# EasyEDA_-_Encoder_Breakout_Schematic.net
KiCad netlist of a schematic drawn in EasyEDA
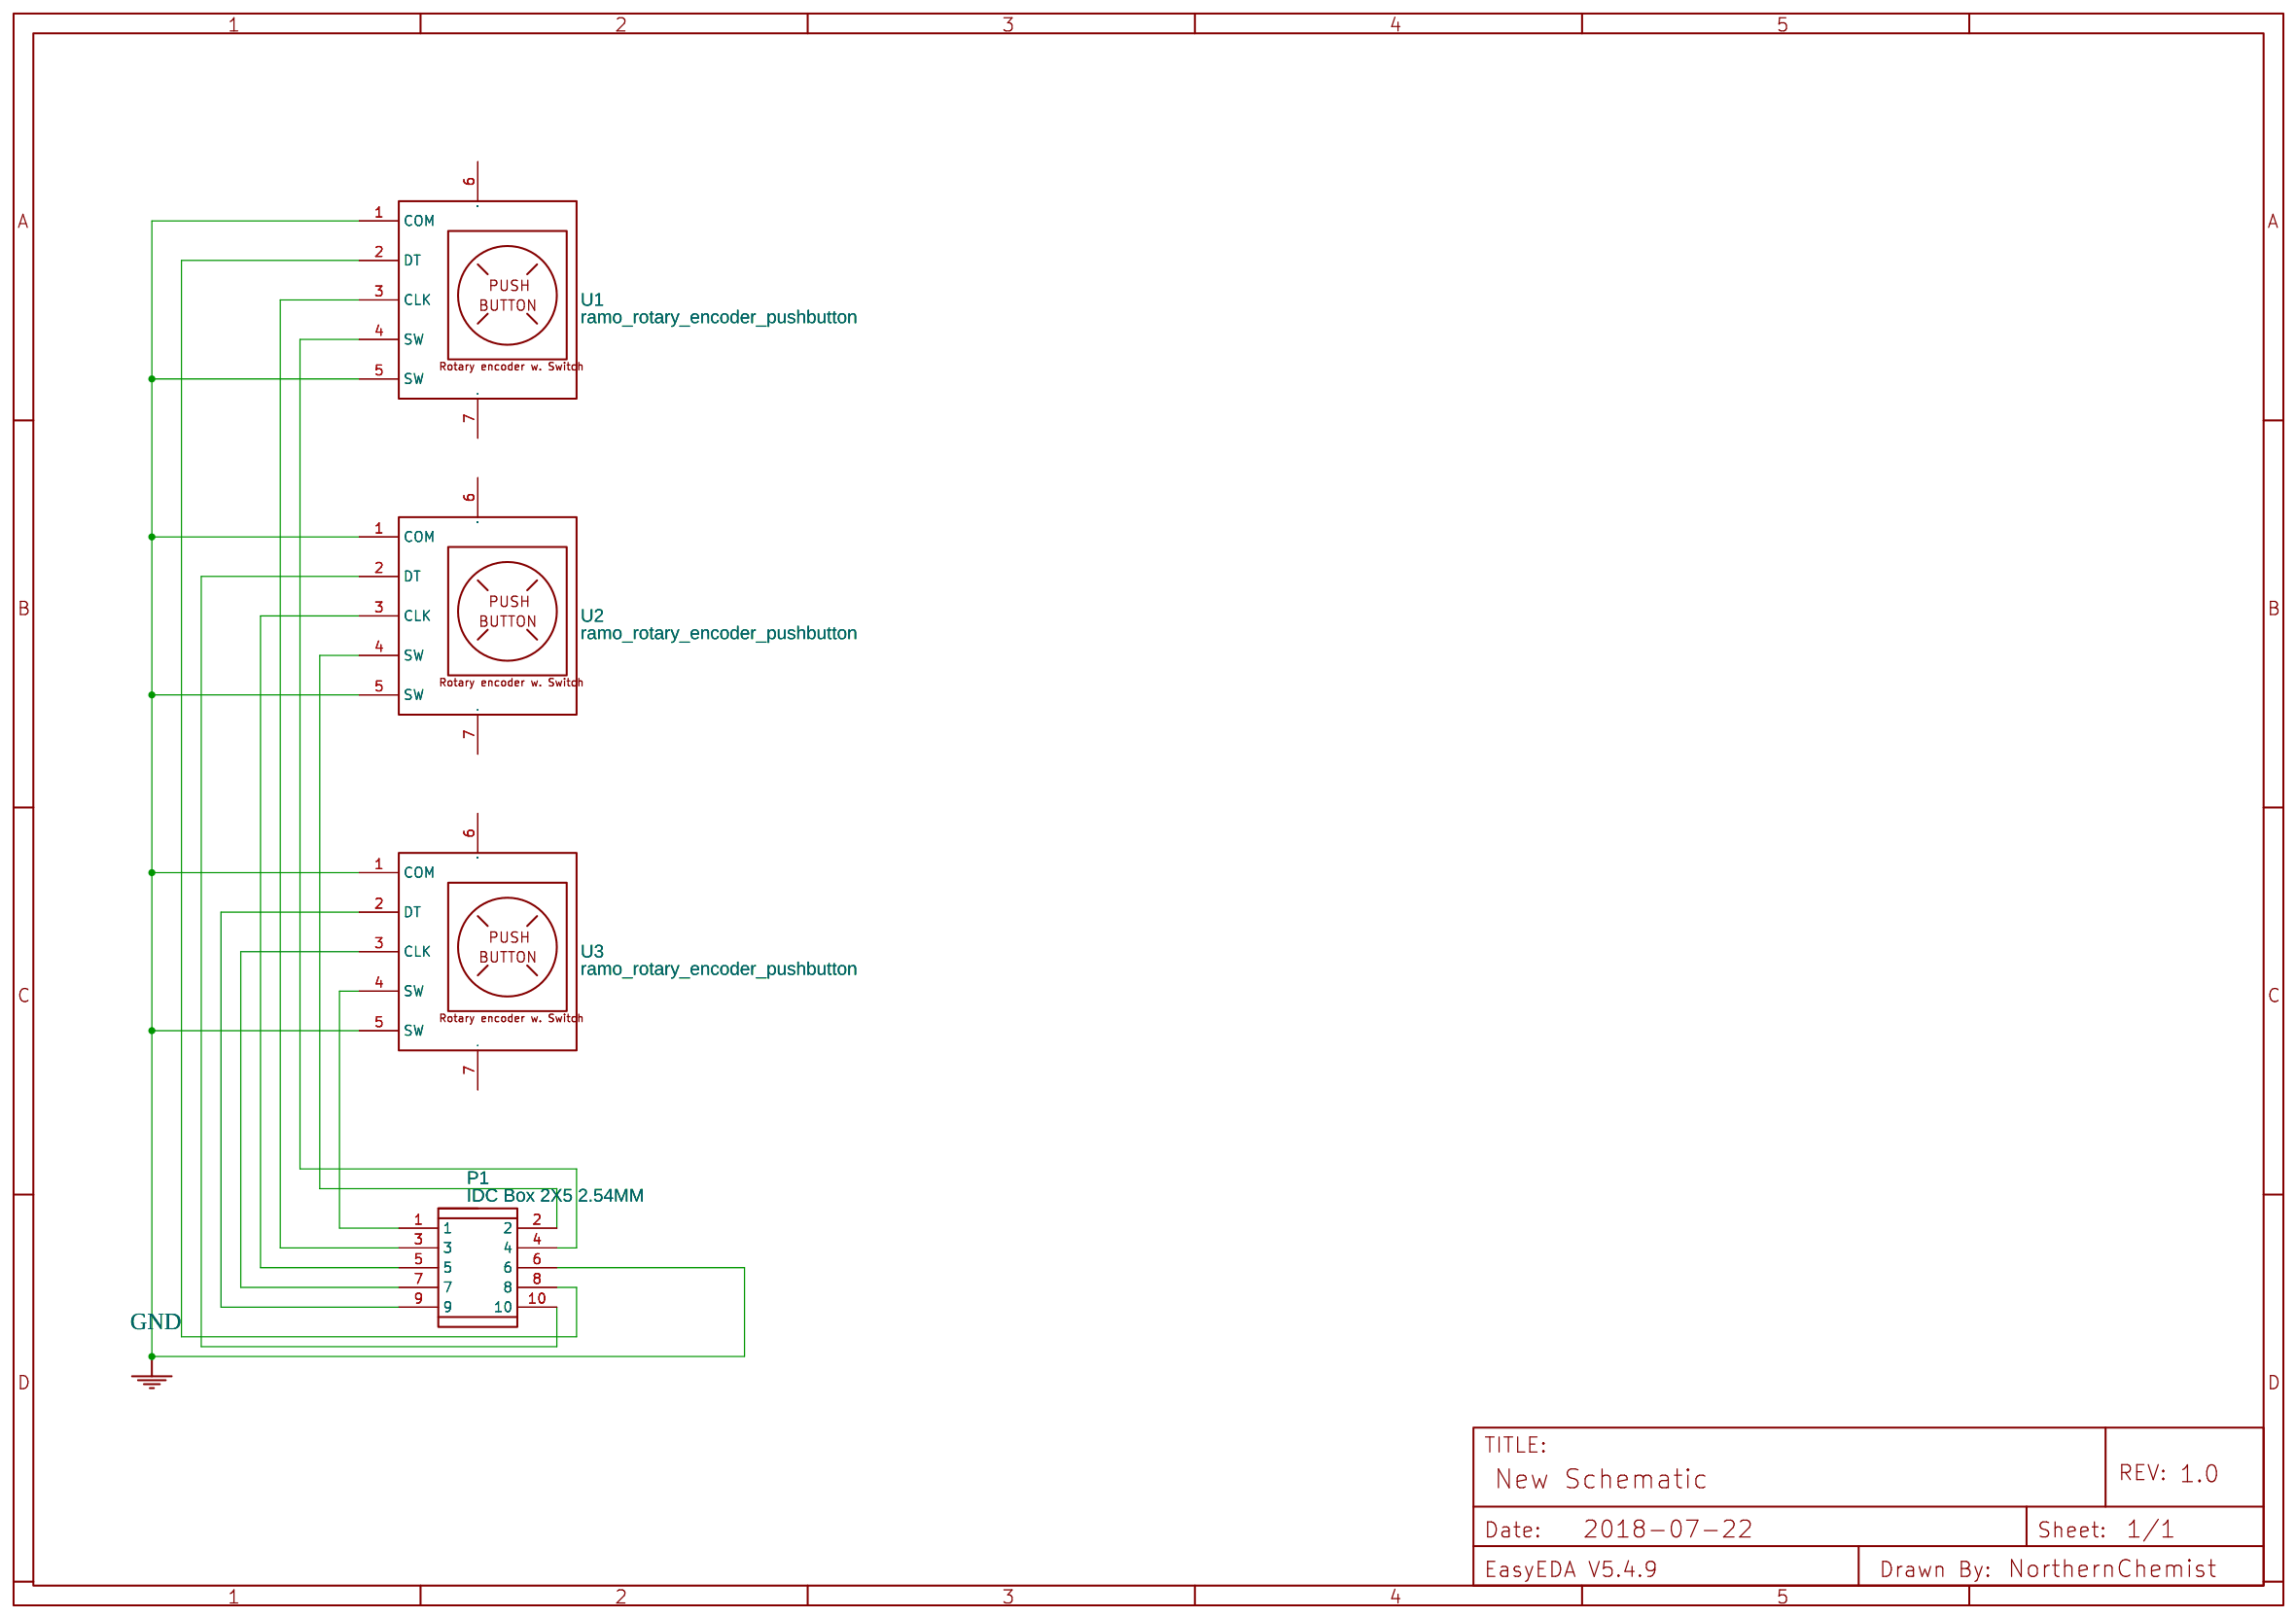
[diagram p0: schematic sheet]

(export (version "E")
  (design (tool "Eeschema 10.0.6"))
  (components
    (comp (ref "P1")
      (value "IDC Box 2X5 2.54MM")
      (fields (field (name "BOM_Supplier Part") "C9140"))
      (libsource (lib "") (part "Unknown_235_635"))
    )
    (comp (ref "U1")
      (value "ramo_rotary_encoder_pushbutton")
      (fields (field (name "BOM_Manufacturer Part") "?"))
      (libsource (lib "") (part "ramo_rotary_encoder_pushbutton"))
    )
    (comp (ref "U2")
      (value "ramo_rotary_encoder_pushbutton")
      (fields (field (name "BOM_Manufacturer Part") "?"))
      (libsource (lib "") (part "ramo_rotary_encoder_pushbutton"))
    )
    (comp (ref "U3")
      (value "ramo_rotary_encoder_pushbutton")
      (fields (field (name "BOM_Manufacturer Part") "?"))
      (libsource (lib "") (part "ramo_rotary_encoder_pushbutton"))
    )
  )
  (nets
    (net (code "1") (name "GND") (class "Default")
      (node (ref "P1") (pin "6") (pinfunction "6_6") (pintype "unspecified"))
      (node (ref "U1") (pin "1") (pinfunction "COM_1") (pintype "unspecified"))
      (node (ref "U1") (pin "5") (pinfunction "SW_5") (pintype "unspecified"))
      (node (ref "U2") (pin "1") (pinfunction "COM_1") (pintype "unspecified"))
      (node (ref "U2") (pin "5") (pinfunction "SW_5") (pintype "unspecified"))
      (node (ref "U3") (pin "1") (pinfunction "COM_1") (pintype "unspecified"))
      (node (ref "U3") (pin "5") (pinfunction "SW_5") (pintype "unspecified"))
    )
    (net (code "2") (name "Net-(P1-Pad1)") (class "Default")
      (node (ref "P1") (pin "1") (pinfunction "1_1") (pintype "unspecified"))
      (node (ref "U3") (pin "4") (pinfunction "SW_4") (pintype "unspecified"))
    )
    (net (code "3") (name "Net-(P1-Pad2)") (class "Default")
      (node (ref "P1") (pin "2") (pinfunction "2_2") (pintype "unspecified"))
      (node (ref "U2") (pin "4") (pinfunction "SW_4") (pintype "unspecified"))
    )
    (net (code "4") (name "Net-(P1-Pad4)") (class "Default")
      (node (ref "P1") (pin "4") (pinfunction "4_4") (pintype "unspecified"))
      (node (ref "U1") (pin "4") (pinfunction "SW_4") (pintype "unspecified"))
    )
    (net (code "5") (name "Net-(U1-CLK)") (class "Default")
      (node (ref "P1") (pin "3") (pinfunction "3_3") (pintype "unspecified"))
      (node (ref "U1") (pin "3") (pinfunction "CLK_3") (pintype "unspecified"))
    )
    (net (code "6") (name "Net-(U1-DT)") (class "Default")
      (node (ref "P1") (pin "8") (pinfunction "8_8") (pintype "unspecified"))
      (node (ref "U1") (pin "2") (pinfunction "DT_2") (pintype "unspecified"))
    )
    (net (code "7") (name "Net-(U2-CLK)") (class "Default")
      (node (ref "P1") (pin "5") (pinfunction "5_5") (pintype "unspecified"))
      (node (ref "U2") (pin "3") (pinfunction "CLK_3") (pintype "unspecified"))
    )
    (net (code "8") (name "Net-(U2-DT)") (class "Default")
      (node (ref "P1") (pin "10") (pinfunction "10_10") (pintype "unspecified"))
      (node (ref "U2") (pin "2") (pinfunction "DT_2") (pintype "unspecified"))
    )
    (net (code "9") (name "Net-(U3-CLK)") (class "Default")
      (node (ref "P1") (pin "7") (pinfunction "7_7") (pintype "unspecified"))
      (node (ref "U3") (pin "3") (pinfunction "CLK_3") (pintype "unspecified"))
    )
    (net (code "10") (name "Net-(U3-DT)") (class "Default")
      (node (ref "P1") (pin "9") (pinfunction "9_9") (pintype "unspecified"))
      (node (ref "U3") (pin "2") (pinfunction "DT_2") (pintype "unspecified"))
    )
    (net (code "11") (name "unconnected-(U1-Pad6)") (class "Default")
      (node (ref "U1") (pin "6") (pinfunction "6_6") (pintype "unspecified"))
    )
    (net (code "12") (name "unconnected-(U1-Pad7)") (class "Default")
      (node (ref "U1") (pin "7") (pinfunction "7_7") (pintype "unspecified"))
    )
    (net (code "13") (name "unconnected-(U2-Pad6)") (class "Default")
      (node (ref "U2") (pin "6") (pinfunction "6_6") (pintype "unspecified"))
    )
    (net (code "14") (name "unconnected-(U2-Pad7)") (class "Default")
      (node (ref "U2") (pin "7") (pinfunction "7_7") (pintype "unspecified"))
    )
    (net (code "15") (name "unconnected-(U3-Pad6)") (class "Default")
      (node (ref "U3") (pin "6") (pinfunction "6_6") (pintype "unspecified"))
    )
    (net (code "16") (name "unconnected-(U3-Pad7)") (class "Default")
      (node (ref "U3") (pin "7") (pinfunction "7_7") (pintype "unspecified"))
    )
  )
)
